# DualLEDDriver.net
KiCad netlist of a schematic drawn in Altium Designer
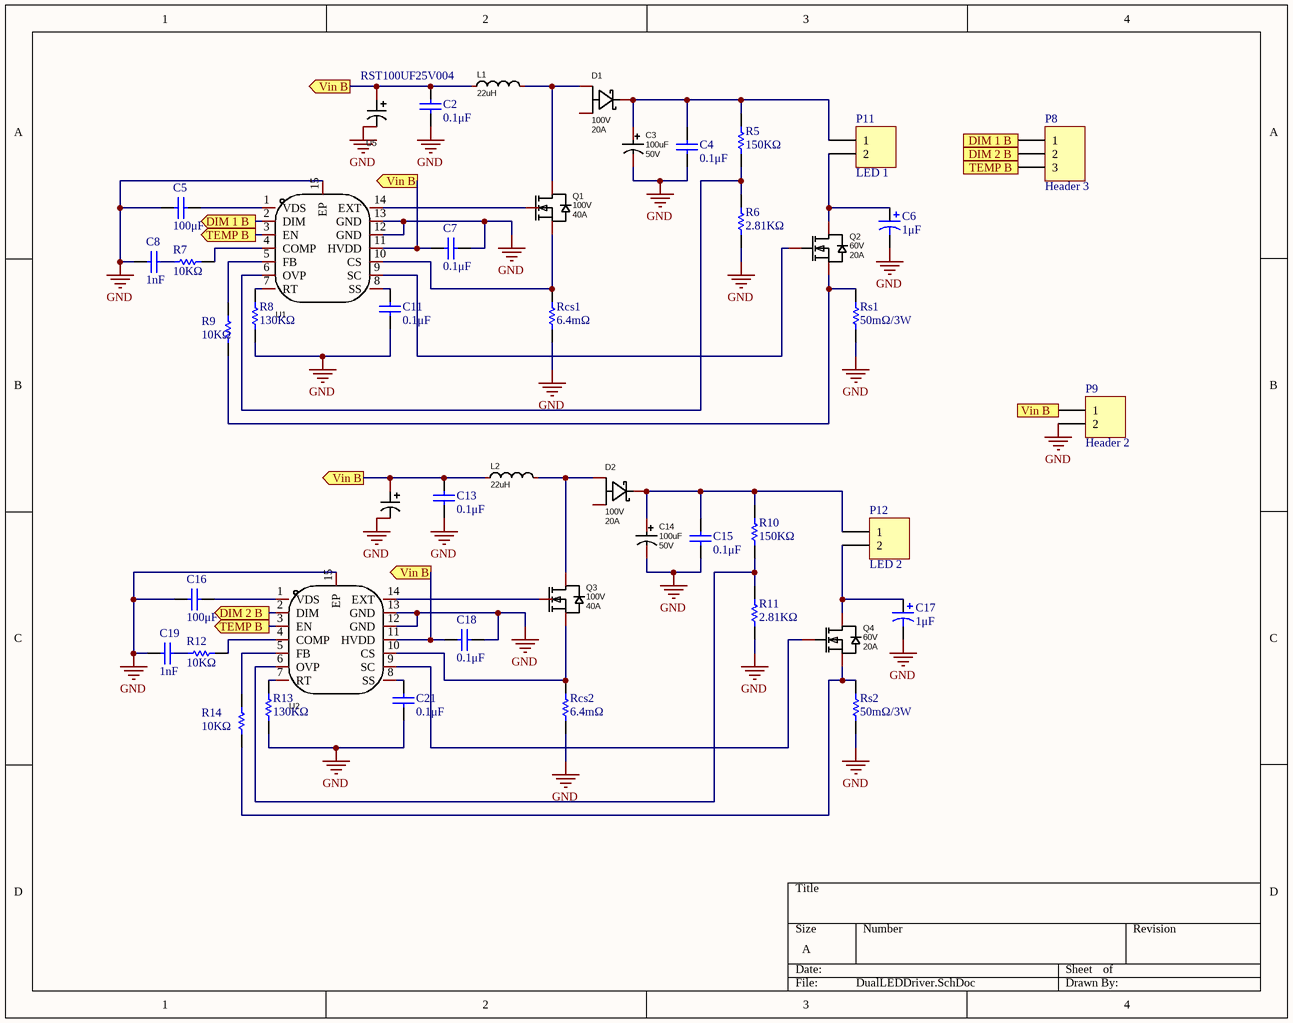
[diagram p0: DualLEDDriver.SchDoc]

(export (version "E")
  (design (tool "Eeschema 10.0.6"))
  (components
    (comp (ref "C2")
      (value "0.1μF")
      (footprint "C0805")
      (description "Capacitor")
      (fields (field (name "Comment") "Cap") (field (name "PUBLISHER") "Altium Limited"))
      (libsource (lib "Miscellaneous Devices") (part "Cap"))
    )
    (comp (ref "C3")
      (value "100uF")
      (footprint "CAP-TH_BD8.0-P3.50-D0.6-FD")
      (fields
        (field (name "MANUFACTURER") "CX(承兴)")
        (field (name "MANUFACTURER PART") "KM107M050F12RR0VH2FP0")
        (field (name "TOLERANCE") "±20%")
        (field (name "RATED VOLTAGE") "50V")
      )
      (libsource (lib "altium-import") (part "root_3_KM107M050F12RR0VH2FP0_"))
    )
    (comp (ref "C4")
      (value "0.1μF")
      (footprint "C0805")
      (description "Capacitor")
      (fields (field (name "Comment") "Cap") (field (name "PUBLISHER") "Altium Limited"))
      (libsource (lib "Miscellaneous Devices") (part "Cap"))
    )
    (comp (ref "C5")
      (value "100μF")
      (footprint "C0805")
      (description "Capacitor")
      (fields (field (name "Comment") "Cap") (field (name "PUBLISHER") "Altium Limited"))
      (libsource (lib "Miscellaneous Devices") (part "Cap"))
    )
    (comp (ref "C6")
      (value "1μF")
      (footprint "C0805")
      (description "Polarized Capacitor (Surface Mount)")
      (fields (field (name "Comment") "Cap Pol3") (field (name "PUBLISHER") "Altium Limited"))
      (libsource (lib "Miscellaneous Devices") (part "Cap Pol3"))
    )
    (comp (ref "C7")
      (value "0.1μF")
      (footprint "C0805")
      (description "Capacitor")
      (fields (field (name "Comment") "Cap") (field (name "PUBLISHER") "Altium Limited"))
      (libsource (lib "Miscellaneous Devices") (part "Cap"))
    )
    (comp (ref "C8")
      (value "1nF")
      (footprint "C0805")
      (description "Capacitor")
      (fields (field (name "Comment") "Cap") (field (name "PUBLISHER") "Altium Limited"))
      (libsource (lib "Miscellaneous Devices") (part "Cap"))
    )
    (comp (ref "C11")
      (value "0.1μF")
      (footprint "C0805")
      (description "Capacitor")
      (fields (field (name "Comment") "Cap") (field (name "PUBLISHER") "Altium Limited"))
      (libsource (lib "Miscellaneous Devices") (part "Cap"))
    )
    (comp (ref "C13")
      (value "0.1μF")
      (footprint "C0805")
      (description "Capacitor")
      (fields (field (name "Comment") "Cap") (field (name "PUBLISHER") "Altium Limited"))
      (libsource (lib "Miscellaneous Devices") (part "Cap"))
    )
    (comp (ref "C14")
      (value "100uF")
      (footprint "CAP-TH_BD8.0-P3.50-D0.6-FD")
      (fields
        (field (name "MANUFACTURER") "CX(承兴)")
        (field (name "MANUFACTURER PART") "KM107M050F12RR0VH2FP0")
        (field (name "TOLERANCE") "±20%")
        (field (name "RATED VOLTAGE") "50V")
      )
      (libsource (lib "altium-import") (part "root_3_KM107M050F12RR0VH2FP0_"))
    )
    (comp (ref "C15")
      (value "0.1μF")
      (footprint "C0805")
      (description "Capacitor")
      (fields (field (name "Comment") "Cap") (field (name "PUBLISHER") "Altium Limited"))
      (libsource (lib "Miscellaneous Devices") (part "Cap"))
    )
    (comp (ref "C16")
      (value "100μF")
      (footprint "C0805")
      (description "Capacitor")
      (fields (field (name "Comment") "Cap") (field (name "PUBLISHER") "Altium Limited"))
      (libsource (lib "Miscellaneous Devices") (part "Cap"))
    )
    (comp (ref "C17")
      (value "1μF")
      (footprint "C0805")
      (description "Polarized Capacitor (Surface Mount)")
      (fields (field (name "Comment") "Cap Pol3") (field (name "PUBLISHER") "Altium Limited"))
      (libsource (lib "Miscellaneous Devices") (part "Cap Pol3"))
    )
    (comp (ref "C18")
      (value "0.1μF")
      (footprint "C0805")
      (description "Capacitor")
      (fields (field (name "Comment") "Cap") (field (name "PUBLISHER") "Altium Limited"))
      (libsource (lib "Miscellaneous Devices") (part "Cap"))
    )
    (comp (ref "C19")
      (value "1nF")
      (footprint "C0805")
      (description "Capacitor")
      (fields (field (name "Comment") "Cap") (field (name "PUBLISHER") "Altium Limited"))
      (libsource (lib "Miscellaneous Devices") (part "Cap"))
    )
    (comp (ref "C21")
      (value "0.1μF")
      (footprint "C0805")
      (description "Capacitor")
      (fields (field (name "Comment") "Cap") (field (name "PUBLISHER") "Altium Limited"))
      (libsource (lib "Miscellaneous Devices") (part "Cap"))
    )
    (comp (ref "D1")
      (value "ST20100L")
      (footprint "TO-277_3P-L5.7-W4.2-LS6.5-BR")
      (fields
        (field (name "MANUFACTURER") "CJ(江苏长电/长晶)")
        (field (name "REVERSE VOLTAGE (VR)") "100V")
        (field (name "AVERAGE RECTIFIED CURRENT (IO)") "20A")
      )
      (libsource (lib "altium-import") (part "root_2_ST20100L_"))
    )
    (comp (ref "D2")
      (value "ST20100L")
      (footprint "TO-277_3P-L5.7-W4.2-LS6.5-BR")
      (fields
        (field (name "MANUFACTURER") "CJ(江苏长电/长晶)")
        (field (name "REVERSE VOLTAGE (VR)") "100V")
        (field (name "AVERAGE RECTIFIED CURRENT (IO)") "20A")
      )
      (libsource (lib "altium-import") (part "root_2_ST20100L_"))
    )
    (comp (ref "L1")
      (value "22uH")
      (footprint "IND-SMD_L16.5-W15.5")
      (fields
        (field (name "MANUFACTURER") "cjiang(长江微电)")
        (field (name "MANUFACTURER PART") "FEXL1513A-220M")
        (field (name "TOLERANCE") "±20%")
      )
      (libsource (lib "altium-import") (part "root_0_FEXL1513A-220M_"))
    )
    (comp (ref "L2")
      (value "22uH")
      (footprint "IND-SMD_L16.5-W15.5")
      (fields
        (field (name "MANUFACTURER") "cjiang(长江微电)")
        (field (name "MANUFACTURER PART") "FEXL1513A-220M")
        (field (name "TOLERANCE") "±20%")
      )
      (libsource (lib "altium-import") (part "root_0_FEXL1513A-220M_"))
    )
    (comp (ref "P8")
      (value "Header 3")
      (footprint "HDR1X3")
      (description "Header, 3-Pin")
      (fields (field (name "PUBLISHER") "Altium Limited"))
      (libsource (lib "Miscellaneous Connectors") (part "Header 3"))
    )
    (comp (ref "P9")
      (value "Header 2")
      (footprint "HDR1X2")
      (description "Header, 2-Pin")
      (fields (field (name "PUBLISHER") "Altium Limited"))
      (libsource (lib "Miscellaneous Connectors") (part "Header 2"))
    )
    (comp (ref "P11")
      (value "LED 1")
      (footprint "HDR1X2")
      (description "Header, 2-Pin")
      (fields (field (name "PUBLISHER") "Altium Limited"))
      (libsource (lib "Miscellaneous Connectors") (part "Header 2"))
    )
    (comp (ref "P12")
      (value "LED 2")
      (footprint "HDR1X2")
      (description "Header, 2-Pin")
      (fields (field (name "PUBLISHER") "Altium Limited"))
      (libsource (lib "Miscellaneous Connectors") (part "Header 2"))
    )
    (comp (ref "Q1")
      (value "AP40T10GH-VB")
      (footprint "TO-252-2_L6.6-W6.1-P4.58-LS9.9-TL")
      (fields
        (field (name "MANUFACTURER") "VBsemi(微碧半导体)")
        (field (name "DRAIN SOURCE VOLTAGE (VDSS)") "100V")
        (field (name "CONTINUOUS DRAIN CURRENT (ID)") "40A")
      )
      (libsource (lib "altium-import") (part "root_0_AP40T10GH-VB_"))
    )
    (comp (ref "Q2")
      (value "NCE6020AK")
      (footprint "TO-252-2_L6.6-W6.1-P4.57-LS10.1-TL-CW")
      (fields
        (field (name "MANUFACTURER") "NCE(无锡新洁能)")
        (field (name "DRAIN SOURCE VOLTAGE (VDSS)") "60V")
        (field (name "CONTINUOUS DRAIN CURRENT (ID)") "20A")
      )
      (libsource (lib "altium-import") (part "root_0_NCE6020AK_"))
    )
    (comp (ref "Q3")
      (value "AP40T10GH-VB")
      (footprint "TO-252-2_L6.6-W6.1-P4.58-LS9.9-TL")
      (fields
        (field (name "MANUFACTURER") "VBsemi(微碧半导体)")
        (field (name "DRAIN SOURCE VOLTAGE (VDSS)") "100V")
        (field (name "CONTINUOUS DRAIN CURRENT (ID)") "40A")
      )
      (libsource (lib "altium-import") (part "root_0_AP40T10GH-VB_"))
    )
    (comp (ref "Q4")
      (value "NCE6020AK")
      (footprint "TO-252-2_L6.6-W6.1-P4.57-LS10.1-TL-CW")
      (fields
        (field (name "MANUFACTURER") "NCE(无锡新洁能)")
        (field (name "DRAIN SOURCE VOLTAGE (VDSS)") "60V")
        (field (name "CONTINUOUS DRAIN CURRENT (ID)") "20A")
      )
      (libsource (lib "altium-import") (part "root_0_NCE6020AK_"))
    )
    (comp (ref "R5")
      (value "150KΩ")
      (footprint "C0805")
      (description "Resistor")
      (fields (field (name "Comment") "Res1") (field (name "PUBLISHER") "Altium Limited"))
      (libsource (lib "Miscellaneous Devices") (part "Res1"))
    )
    (comp (ref "R6")
      (value "2.81KΩ")
      (footprint "C0805")
      (description "Resistor")
      (fields (field (name "Comment") "Res1") (field (name "PUBLISHER") "Altium Limited"))
      (libsource (lib "Miscellaneous Devices") (part "Res1"))
    )
    (comp (ref "R7")
      (value "10KΩ")
      (footprint "C0805")
      (description "Resistor")
      (fields (field (name "Comment") "Res1") (field (name "PUBLISHER") "Altium Limited"))
      (libsource (lib "Miscellaneous Devices") (part "Res1"))
    )
    (comp (ref "R8")
      (value "130KΩ")
      (footprint "C0805")
      (description "Resistor")
      (fields (field (name "Comment") "Res1") (field (name "PUBLISHER") "Altium Limited"))
      (libsource (lib "Miscellaneous Devices") (part "Res1"))
    )
    (comp (ref "R9")
      (value "10KΩ")
      (footprint "C0805")
      (description "Resistor")
      (fields (field (name "Comment") "Res1") (field (name "PUBLISHER") "Altium Limited"))
      (libsource (lib "Miscellaneous Devices") (part "Res1"))
    )
    (comp (ref "R10")
      (value "150KΩ")
      (footprint "C0805")
      (description "Resistor")
      (fields (field (name "Comment") "Res1") (field (name "PUBLISHER") "Altium Limited"))
      (libsource (lib "Miscellaneous Devices") (part "Res1"))
    )
    (comp (ref "R11")
      (value "2.81KΩ")
      (footprint "C0805")
      (description "Resistor")
      (fields (field (name "Comment") "Res1") (field (name "PUBLISHER") "Altium Limited"))
      (libsource (lib "Miscellaneous Devices") (part "Res1"))
    )
    (comp (ref "R12")
      (value "10KΩ")
      (footprint "C0805")
      (description "Resistor")
      (fields (field (name "Comment") "Res1") (field (name "PUBLISHER") "Altium Limited"))
      (libsource (lib "Miscellaneous Devices") (part "Res1"))
    )
    (comp (ref "R13")
      (value "130KΩ")
      (footprint "C0805")
      (description "Resistor")
      (fields (field (name "Comment") "Res1") (field (name "PUBLISHER") "Altium Limited"))
      (libsource (lib "Miscellaneous Devices") (part "Res1"))
    )
    (comp (ref "R14")
      (value "10KΩ")
      (footprint "C0805")
      (description "Resistor")
      (fields (field (name "Comment") "Res1") (field (name "PUBLISHER") "Altium Limited"))
      (libsource (lib "Miscellaneous Devices") (part "Res1"))
    )
    (comp (ref "Rcs1")
      (value "6.4mΩ")
      (footprint "C0805")
      (description "Resistor")
      (fields (field (name "Comment") "Res1") (field (name "PUBLISHER") "Altium Limited"))
      (libsource (lib "Miscellaneous Devices") (part "Res1"))
    )
    (comp (ref "Rcs2")
      (value "6.4mΩ")
      (footprint "C0805")
      (description "Resistor")
      (fields (field (name "Comment") "Res1") (field (name "PUBLISHER") "Altium Limited"))
      (libsource (lib "Miscellaneous Devices") (part "Res1"))
    )
    (comp (ref "Rs1")
      (value "50mΩ/3W")
      (footprint "C2512")
      (description "Resistor")
      (fields (field (name "Comment") "Res1") (field (name "PUBLISHER") "Altium Limited"))
      (libsource (lib "Miscellaneous Devices") (part "Res1"))
    )
    (comp (ref "Rs2")
      (value "50mΩ/3W")
      (footprint "C2512")
      (description "Resistor")
      (fields (field (name "Comment") "Res1") (field (name "PUBLISHER") "Altium Limited"))
      (libsource (lib "Miscellaneous Devices") (part "Res1"))
    )
    (comp (ref "U1")
      (value "FP7209mR-G1")
      (footprint "TSSOP-14_L5.0-W4.4-P0.65-LS6.4-BL-EP")
      (fields (field (name "MANUFACTURER") "Advanced Analog Technology(类比)"))
      (libsource (lib "altium-import") (part "root_0_FP7209mR-G1_"))
    )
    (comp (ref "U2")
      (value "FP7209mR-G1")
      (footprint "TSSOP-14_L5.0-W4.4-P0.65-LS6.4-BL-EP")
      (fields (field (name "MANUFACTURER") "Advanced Analog Technology(类比)"))
      (libsource (lib "altium-import") (part "root_0_FP7209mR-G1_"))
    )
    (comp (ref "U5")
      (value "RST100UF25V004")
      (footprint "CAP-SMD_BD6.3-L6.6-W6.6-LS7.3-FD")
      (fields (field (name "MANUFACTURER") "KNSCHA(科尼盛)") (field (name "TOLERANCE") "±20%"))
      (libsource (lib "altium-import") (part "root_3_RST100UF25V004_"))
    )
    (comp (ref "U6")
      (value "RST100UF25V004")
      (footprint "CAP-SMD_BD6.3-L6.6-W6.6-LS7.3-FD")
      (fields (field (name "MANUFACTURER") "KNSCHA(科尼盛)") (field (name "TOLERANCE") "±20%"))
      (libsource (lib "altium-import") (part "root_3_RST100UF25V004_"))
    )
  )
  (nets
    (net (code "1") (name "/DIM 1 B") (class "Default")
      (node (ref "P8") (pin "1") (pinfunction "1_1") (pintype "passive"))
      (node (ref "U1") (pin "2") (pinfunction "DIM_2") (pintype "passive"))
    )
    (net (code "2") (name "/DIM 2 B") (class "Default")
      (node (ref "P8") (pin "2") (pinfunction "2_2") (pintype "passive"))
      (node (ref "U2") (pin "2") (pinfunction "DIM_2") (pintype "passive"))
    )
    (net (code "3") (name "/TEMP B") (class "Default")
      (node (ref "P8") (pin "3") (pinfunction "3_3") (pintype "passive"))
      (node (ref "U1") (pin "3") (pinfunction "EN_3") (pintype "passive"))
      (node (ref "U2") (pin "3") (pinfunction "EN_3") (pintype "passive"))
    )
    (net (code "4") (name "/Vin B") (class "Default")
      (node (ref "C13") (pin "2") (pinfunction "2_2") (pintype "passive"))
      (node (ref "C18") (pin "2") (pinfunction "2_2") (pintype "passive"))
      (node (ref "C2") (pin "2") (pinfunction "2_2") (pintype "passive"))
      (node (ref "C7") (pin "2") (pinfunction "2_2") (pintype "passive"))
      (node (ref "L1") (pin "2") (pinfunction "2_2") (pintype "passive"))
      (node (ref "L2") (pin "2") (pinfunction "2_2") (pintype "passive"))
      (node (ref "P9") (pin "1") (pinfunction "1_1") (pintype "passive"))
      (node (ref "U1") (pin "11") (pinfunction "HVDD_11") (pintype "passive"))
      (node (ref "U2") (pin "11") (pinfunction "HVDD_11") (pintype "passive"))
      (node (ref "U5") (pin "1") (pinfunction "1_1") (pintype "passive"))
      (node (ref "U6") (pin "1") (pinfunction "1_1") (pintype "passive"))
    )
    (net (code "5") (name "GND") (class "Default")
      (node (ref "C11") (pin "1") (pinfunction "1_1") (pintype "passive"))
      (node (ref "C13") (pin "1") (pinfunction "1_1") (pintype "passive"))
      (node (ref "C14") (pin "2") (pinfunction "2_2") (pintype "passive"))
      (node (ref "C15") (pin "1") (pinfunction "1_1") (pintype "passive"))
      (node (ref "C16") (pin "2") (pinfunction "2_2") (pintype "passive"))
      (node (ref "C17") (pin "2") (pinfunction "2_2") (pintype "passive"))
      (node (ref "C18") (pin "1") (pinfunction "1_1") (pintype "passive"))
      (node (ref "C19") (pin "2") (pinfunction "2_2") (pintype "passive"))
      (node (ref "C2") (pin "1") (pinfunction "1_1") (pintype "passive"))
      (node (ref "C21") (pin "1") (pinfunction "1_1") (pintype "passive"))
      (node (ref "C3") (pin "2") (pinfunction "2_2") (pintype "passive"))
      (node (ref "C4") (pin "1") (pinfunction "1_1") (pintype "passive"))
      (node (ref "C5") (pin "2") (pinfunction "2_2") (pintype "passive"))
      (node (ref "C6") (pin "2") (pinfunction "2_2") (pintype "passive"))
      (node (ref "C7") (pin "1") (pinfunction "1_1") (pintype "passive"))
      (node (ref "C8") (pin "2") (pinfunction "2_2") (pintype "passive"))
      (node (ref "P9") (pin "2") (pinfunction "2_2") (pintype "passive"))
      (node (ref "R11") (pin "2") (pinfunction "2_2") (pintype "passive"))
      (node (ref "R13") (pin "1") (pinfunction "1_1") (pintype "passive"))
      (node (ref "R6") (pin "2") (pinfunction "2_2") (pintype "passive"))
      (node (ref "R8") (pin "1") (pinfunction "1_1") (pintype "passive"))
      (node (ref "Rcs1") (pin "1") (pinfunction "1_1") (pintype "passive"))
      (node (ref "Rcs2") (pin "1") (pinfunction "1_1") (pintype "passive"))
      (node (ref "Rs1") (pin "1") (pinfunction "1_1") (pintype "passive"))
      (node (ref "Rs2") (pin "1") (pinfunction "1_1") (pintype "passive"))
      (node (ref "U1") (pin "12") (pinfunction "GND_12") (pintype "passive"))
      (node (ref "U1") (pin "13") (pinfunction "GND_13") (pintype "passive"))
      (node (ref "U1") (pin "15") (pinfunction "EP_15") (pintype "passive"))
      (node (ref "U2") (pin "12") (pinfunction "GND_12") (pintype "passive"))
      (node (ref "U2") (pin "13") (pinfunction "GND_13") (pintype "passive"))
      (node (ref "U2") (pin "15") (pinfunction "EP_15") (pintype "passive"))
      (node (ref "U5") (pin "2") (pinfunction "2_2") (pintype "passive"))
      (node (ref "U6") (pin "2") (pinfunction "2_2") (pintype "passive"))
    )
    (net (code "6") (name "Net-(C8-Pad1)") (class "Default")
      (node (ref "C8") (pin "1") (pinfunction "1_1") (pintype "passive"))
      (node (ref "R7") (pin "1") (pinfunction "1_1") (pintype "passive"))
    )
    (net (code "7") (name "Net-(C19-Pad1)") (class "Default")
      (node (ref "C19") (pin "1") (pinfunction "1_1") (pintype "passive"))
      (node (ref "R12") (pin "1") (pinfunction "1_1") (pintype "passive"))
    )
    (net (code "8") (name "Net-(D1-K)") (class "Default")
      (node (ref "C3") (pin "1") (pinfunction "1_1") (pintype "passive"))
      (node (ref "C4") (pin "2") (pinfunction "2_2") (pintype "passive"))
      (node (ref "D1") (pin "2") (pinfunction "K_2") (pintype "passive"))
      (node (ref "P11") (pin "1") (pinfunction "1_1") (pintype "passive"))
      (node (ref "R5") (pin "2") (pinfunction "2_2") (pintype "passive"))
    )
    (net (code "9") (name "Net-(D2-K)") (class "Default")
      (node (ref "C14") (pin "1") (pinfunction "1_1") (pintype "passive"))
      (node (ref "C15") (pin "2") (pinfunction "2_2") (pintype "passive"))
      (node (ref "D2") (pin "2") (pinfunction "K_2") (pintype "passive"))
      (node (ref "P12") (pin "1") (pinfunction "1_1") (pintype "passive"))
      (node (ref "R10") (pin "2") (pinfunction "2_2") (pintype "passive"))
    )
    (net (code "10") (name "Net-(Q1-D)") (class "Default")
      (node (ref "D1") (pin "1") (pinfunction "A_1") (pintype "passive"))
      (node (ref "L1") (pin "1") (pinfunction "1_1") (pintype "passive"))
      (node (ref "Q1") (pin "2") (pinfunction "D_2") (pintype "passive"))
    )
    (net (code "11") (name "Net-(Q1-G)") (class "Default")
      (node (ref "Q1") (pin "1") (pinfunction "G_1") (pintype "passive"))
      (node (ref "U1") (pin "14") (pinfunction "EXT_14") (pintype "passive"))
    )
    (net (code "12") (name "Net-(Q1-S)") (class "Default")
      (node (ref "Q1") (pin "3") (pinfunction "S_3") (pintype "passive"))
      (node (ref "Rcs1") (pin "2") (pinfunction "2_2") (pintype "passive"))
      (node (ref "U1") (pin "10") (pinfunction "CS_10") (pintype "passive"))
    )
    (net (code "13") (name "Net-(Q2-D)") (class "Default")
      (node (ref "C6") (pin "1") (pinfunction "1_1") (pintype "passive"))
      (node (ref "P11") (pin "2") (pinfunction "2_2") (pintype "passive"))
      (node (ref "Q2") (pin "2") (pinfunction "D_2") (pintype "passive"))
    )
    (net (code "14") (name "Net-(Q2-G)") (class "Default")
      (node (ref "Q2") (pin "1") (pinfunction "G_1") (pintype "passive"))
      (node (ref "U1") (pin "9") (pinfunction "SC_9") (pintype "passive"))
    )
    (net (code "15") (name "Net-(Q2-S)") (class "Default")
      (node (ref "Q2") (pin "3") (pinfunction "S_3") (pintype "passive"))
      (node (ref "R9") (pin "1") (pinfunction "1_1") (pintype "passive"))
      (node (ref "Rs1") (pin "2") (pinfunction "2_2") (pintype "passive"))
    )
    (net (code "16") (name "Net-(Q3-D)") (class "Default")
      (node (ref "D2") (pin "1") (pinfunction "A_1") (pintype "passive"))
      (node (ref "L2") (pin "1") (pinfunction "1_1") (pintype "passive"))
      (node (ref "Q3") (pin "2") (pinfunction "D_2") (pintype "passive"))
    )
    (net (code "17") (name "Net-(Q3-G)") (class "Default")
      (node (ref "Q3") (pin "1") (pinfunction "G_1") (pintype "passive"))
      (node (ref "U2") (pin "14") (pinfunction "EXT_14") (pintype "passive"))
    )
    (net (code "18") (name "Net-(Q3-S)") (class "Default")
      (node (ref "Q3") (pin "3") (pinfunction "S_3") (pintype "passive"))
      (node (ref "Rcs2") (pin "2") (pinfunction "2_2") (pintype "passive"))
      (node (ref "U2") (pin "10") (pinfunction "CS_10") (pintype "passive"))
    )
    (net (code "19") (name "Net-(Q4-D)") (class "Default")
      (node (ref "C17") (pin "1") (pinfunction "1_1") (pintype "passive"))
      (node (ref "P12") (pin "2") (pinfunction "2_2") (pintype "passive"))
      (node (ref "Q4") (pin "2") (pinfunction "D_2") (pintype "passive"))
    )
    (net (code "20") (name "Net-(Q4-G)") (class "Default")
      (node (ref "Q4") (pin "1") (pinfunction "G_1") (pintype "passive"))
      (node (ref "U2") (pin "9") (pinfunction "SC_9") (pintype "passive"))
    )
    (net (code "21") (name "Net-(Q4-S)") (class "Default")
      (node (ref "Q4") (pin "3") (pinfunction "S_3") (pintype "passive"))
      (node (ref "R14") (pin "1") (pinfunction "1_1") (pintype "passive"))
      (node (ref "Rs2") (pin "2") (pinfunction "2_2") (pintype "passive"))
    )
    (net (code "22") (name "Net-(U1-COMP)") (class "Default")
      (node (ref "R7") (pin "2") (pinfunction "2_2") (pintype "passive"))
      (node (ref "U1") (pin "4") (pinfunction "COMP_4") (pintype "passive"))
    )
    (net (code "23") (name "Net-(U1-FB)") (class "Default")
      (node (ref "R9") (pin "2") (pinfunction "2_2") (pintype "passive"))
      (node (ref "U1") (pin "5") (pinfunction "FB_5") (pintype "passive"))
    )
    (net (code "24") (name "Net-(U1-OVP)") (class "Default")
      (node (ref "R5") (pin "1") (pinfunction "1_1") (pintype "passive"))
      (node (ref "R6") (pin "1") (pinfunction "1_1") (pintype "passive"))
      (node (ref "U1") (pin "6") (pinfunction "OVP_6") (pintype "passive"))
    )
    (net (code "25") (name "Net-(U1-RT)") (class "Default")
      (node (ref "R8") (pin "2") (pinfunction "2_2") (pintype "passive"))
      (node (ref "U1") (pin "7") (pinfunction "RT_7") (pintype "passive"))
    )
    (net (code "26") (name "Net-(U1-SS)") (class "Default")
      (node (ref "C11") (pin "2") (pinfunction "2_2") (pintype "passive"))
      (node (ref "U1") (pin "8") (pinfunction "SS_8") (pintype "passive"))
    )
    (net (code "27") (name "Net-(U1-VDS)") (class "Default")
      (node (ref "C5") (pin "1") (pinfunction "1_1") (pintype "passive"))
      (node (ref "U1") (pin "1") (pinfunction "VDS_1") (pintype "passive"))
    )
    (net (code "28") (name "Net-(U2-COMP)") (class "Default")
      (node (ref "R12") (pin "2") (pinfunction "2_2") (pintype "passive"))
      (node (ref "U2") (pin "4") (pinfunction "COMP_4") (pintype "passive"))
    )
    (net (code "29") (name "Net-(U2-FB)") (class "Default")
      (node (ref "R14") (pin "2") (pinfunction "2_2") (pintype "passive"))
      (node (ref "U2") (pin "5") (pinfunction "FB_5") (pintype "passive"))
    )
    (net (code "30") (name "Net-(U2-OVP)") (class "Default")
      (node (ref "R10") (pin "1") (pinfunction "1_1") (pintype "passive"))
      (node (ref "R11") (pin "1") (pinfunction "1_1") (pintype "passive"))
      (node (ref "U2") (pin "6") (pinfunction "OVP_6") (pintype "passive"))
    )
    (net (code "31") (name "Net-(U2-RT)") (class "Default")
      (node (ref "R13") (pin "2") (pinfunction "2_2") (pintype "passive"))
      (node (ref "U2") (pin "7") (pinfunction "RT_7") (pintype "passive"))
    )
    (net (code "32") (name "Net-(U2-SS)") (class "Default")
      (node (ref "C21") (pin "2") (pinfunction "2_2") (pintype "passive"))
      (node (ref "U2") (pin "8") (pinfunction "SS_8") (pintype "passive"))
    )
    (net (code "33") (name "Net-(U2-VDS)") (class "Default")
      (node (ref "C16") (pin "1") (pinfunction "1_1") (pintype "passive"))
      (node (ref "U2") (pin "1") (pinfunction "VDS_1") (pintype "passive"))
    )
    (net (code "34") (name "unconnected-(D1-A-Pad3)") (class "Default")
      (node (ref "D1") (pin "3") (pinfunction "A_3") (pintype "passive"))
    )
    (net (code "35") (name "unconnected-(D2-A-Pad3)") (class "Default")
      (node (ref "D2") (pin "3") (pinfunction "A_3") (pintype "passive"))
    )
  )
)
